# Sonar_Gonderici_Sheet1.net
KiCad netlist of a schematic drawn in Altium Designer
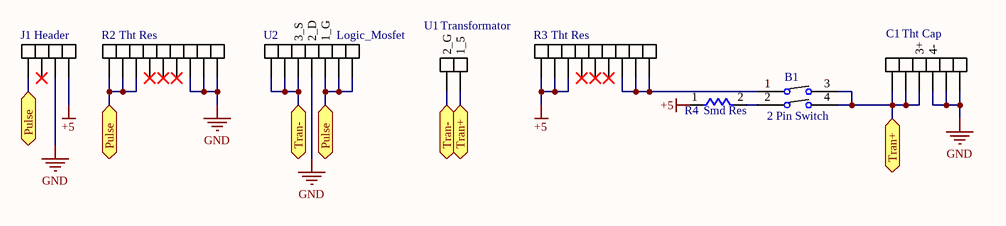
[diagram p0: Sonar_Gonderici_Sheet1.SchDoc]

(export (version "E")
  (design (tool "Eeschema 10.0.6"))
  (components
    (comp (ref "B1")
      (value "2 Pin Switch")
      (footprint "2 Pin Switch")
      (libsource (lib "Sonar_Gonderici_Schlib1") (part "2 Pin Switch"))
    )
    (comp (ref "C1")
      (value "Tht Cap")
      (footprint "THT CAP POL")
      (libsource (lib "Sonar_Gonderici_Schlib1") (part "Tht Cap"))
    )
    (comp (ref "J1")
      (value "Header")
      (footprint "Header")
      (libsource (lib "Sonar_Gonderici_Schlib1") (part "Header"))
    )
    (comp (ref "R2")
      (value "Tht Res")
      (footprint "THT Res")
      (libsource (lib "Sonar_Gonderici_Schlib1") (part "Tht Res"))
    )
    (comp (ref "R3")
      (value "Tht Res")
      (footprint "THT Res")
      (libsource (lib "Sonar_Gonderici_Schlib1") (part "Tht Res"))
    )
    (comp (ref "R4")
      (value "Smd Res")
      (footprint "RESC1005X40")
      (libsource (lib "Sonar_Gonderici_Schlib1") (part "Smd Res"))
    )
    (comp (ref "U1")
      (value "Transformator")
      (footprint "Transfornator")
      (libsource (lib "Sonar_Gonderici_Schlib1") (part "Transformator"))
    )
    (comp (ref "U2")
      (value "Logic_Mosfet")
      (footprint "Logic_Mosfet")
      (libsource (lib "Sonar_Gonderici_Schlib1") (part "Logic_Mosfet"))
    )
  )
  (nets
    (net (code "1") (name "+5") (class "Default")
      (node (ref "J1") (pin "4") (pinfunction "4_4") (pintype "passive"))
      (node (ref "R3") (pin "7") (pinfunction "7_7") (pintype "passive"))
      (node (ref "R3") (pin "8") (pinfunction "8_8") (pintype "passive"))
      (node (ref "R3") (pin "9") (pinfunction "9_9") (pintype "passive"))
      (node (ref "R4") (pin "1") (pinfunction "1_1") (pintype "passive"))
    )
    (net (code "2") (name "/Pulse") (class "Default")
      (node (ref "J1") (pin "1") (pinfunction "1_1") (pintype "passive"))
      (node (ref "R2") (pin "7") (pinfunction "7_7") (pintype "passive"))
      (node (ref "R2") (pin "8") (pinfunction "8_8") (pintype "passive"))
      (node (ref "R2") (pin "9") (pinfunction "9_9") (pintype "passive"))
      (node (ref "U2") (pin "1") (pinfunction "1_1") (pintype "passive"))
      (node (ref "U2") (pin "2") (pinfunction "2_2") (pintype "passive"))
      (node (ref "U2") (pin "3") (pinfunction "1_G_3") (pintype "passive"))
    )
    (net (code "3") (name "/Tran+") (class "Default")
      (node (ref "B1") (pin "3") (pinfunction "3_3") (pintype "passive"))
      (node (ref "B1") (pin "4") (pinfunction "4_4") (pintype "passive"))
      (node (ref "C1") (pin "1") (pinfunction "1_1") (pintype "passive"))
      (node (ref "C1") (pin "2") (pinfunction "2_2") (pintype "passive"))
      (node (ref "C1") (pin "3") (pinfunction "3+_3") (pintype "passive"))
      (node (ref "U1") (pin "1") (pinfunction "1_5_1") (pintype "passive"))
    )
    (net (code "4") (name "/Tran-") (class "Default")
      (node (ref "U1") (pin "2") (pinfunction "2_G_2") (pintype "passive"))
      (node (ref "U2") (pin "5") (pinfunction "3_S_5") (pintype "passive"))
      (node (ref "U2") (pin "6") (pinfunction "6_6") (pintype "passive"))
      (node (ref "U2") (pin "7") (pinfunction "7_7") (pintype "passive"))
    )
    (net (code "5") (name "GND") (class "Default")
      (node (ref "C1") (pin "4") (pinfunction "4-_4") (pintype "passive"))
      (node (ref "C1") (pin "5") (pinfunction "5_5") (pintype "passive"))
      (node (ref "C1") (pin "6") (pinfunction "6_6") (pintype "passive"))
      (node (ref "J1") (pin "3") (pinfunction "3_3") (pintype "passive"))
      (node (ref "R2") (pin "1") (pinfunction "1_1") (pintype "passive"))
      (node (ref "R2") (pin "2") (pinfunction "2_2") (pintype "passive"))
      (node (ref "R2") (pin "3") (pinfunction "3_3") (pintype "passive"))
      (node (ref "U2") (pin "4") (pinfunction "2_D_4") (pintype "passive"))
    )
    (net (code "6") (name "Net-(B1-Pad1)") (class "Default")
      (node (ref "B1") (pin "1") (pinfunction "1_1") (pintype "passive"))
      (node (ref "R3") (pin "1") (pinfunction "1_1") (pintype "passive"))
      (node (ref "R3") (pin "2") (pinfunction "2_2") (pintype "passive"))
      (node (ref "R3") (pin "3") (pinfunction "3_3") (pintype "passive"))
    )
    (net (code "7") (name "Net-(B1-Pad2)") (class "Default")
      (node (ref "B1") (pin "2") (pinfunction "2_2") (pintype "passive"))
      (node (ref "R4") (pin "2") (pinfunction "2_2") (pintype "passive"))
    )
    (net (code "8") (name "unconnected-(J1-Pad1)") (class "Default")
      (node (ref "J1") (pin "1") (pinfunction "1_1") (pintype "passive+no_connect"))
    )
    (net (code "9") (name "unconnected-(R2-Pad4)") (class "Default")
      (node (ref "R2") (pin "4") (pinfunction "4_4") (pintype "passive+no_connect"))
    )
    (net (code "10") (name "unconnected-(R2-Pad5)") (class "Default")
      (node (ref "R2") (pin "5") (pinfunction "5_5") (pintype "passive+no_connect"))
    )
    (net (code "11") (name "unconnected-(R2-Pad6)") (class "Default")
      (node (ref "R2") (pin "6") (pinfunction "6_6") (pintype "passive+no_connect"))
    )
    (net (code "12") (name "unconnected-(R3-Pad4)") (class "Default")
      (node (ref "R3") (pin "4") (pinfunction "4_4") (pintype "passive+no_connect"))
    )
    (net (code "13") (name "unconnected-(R3-Pad5)") (class "Default")
      (node (ref "R3") (pin "5") (pinfunction "5_5") (pintype "passive+no_connect"))
    )
    (net (code "14") (name "unconnected-(R3-Pad6)") (class "Default")
      (node (ref "R3") (pin "6") (pinfunction "6_6") (pintype "passive+no_connect"))
    )
  )
)
